# openfc.net
KiCad netlist of a schematic drawn in EAGLE
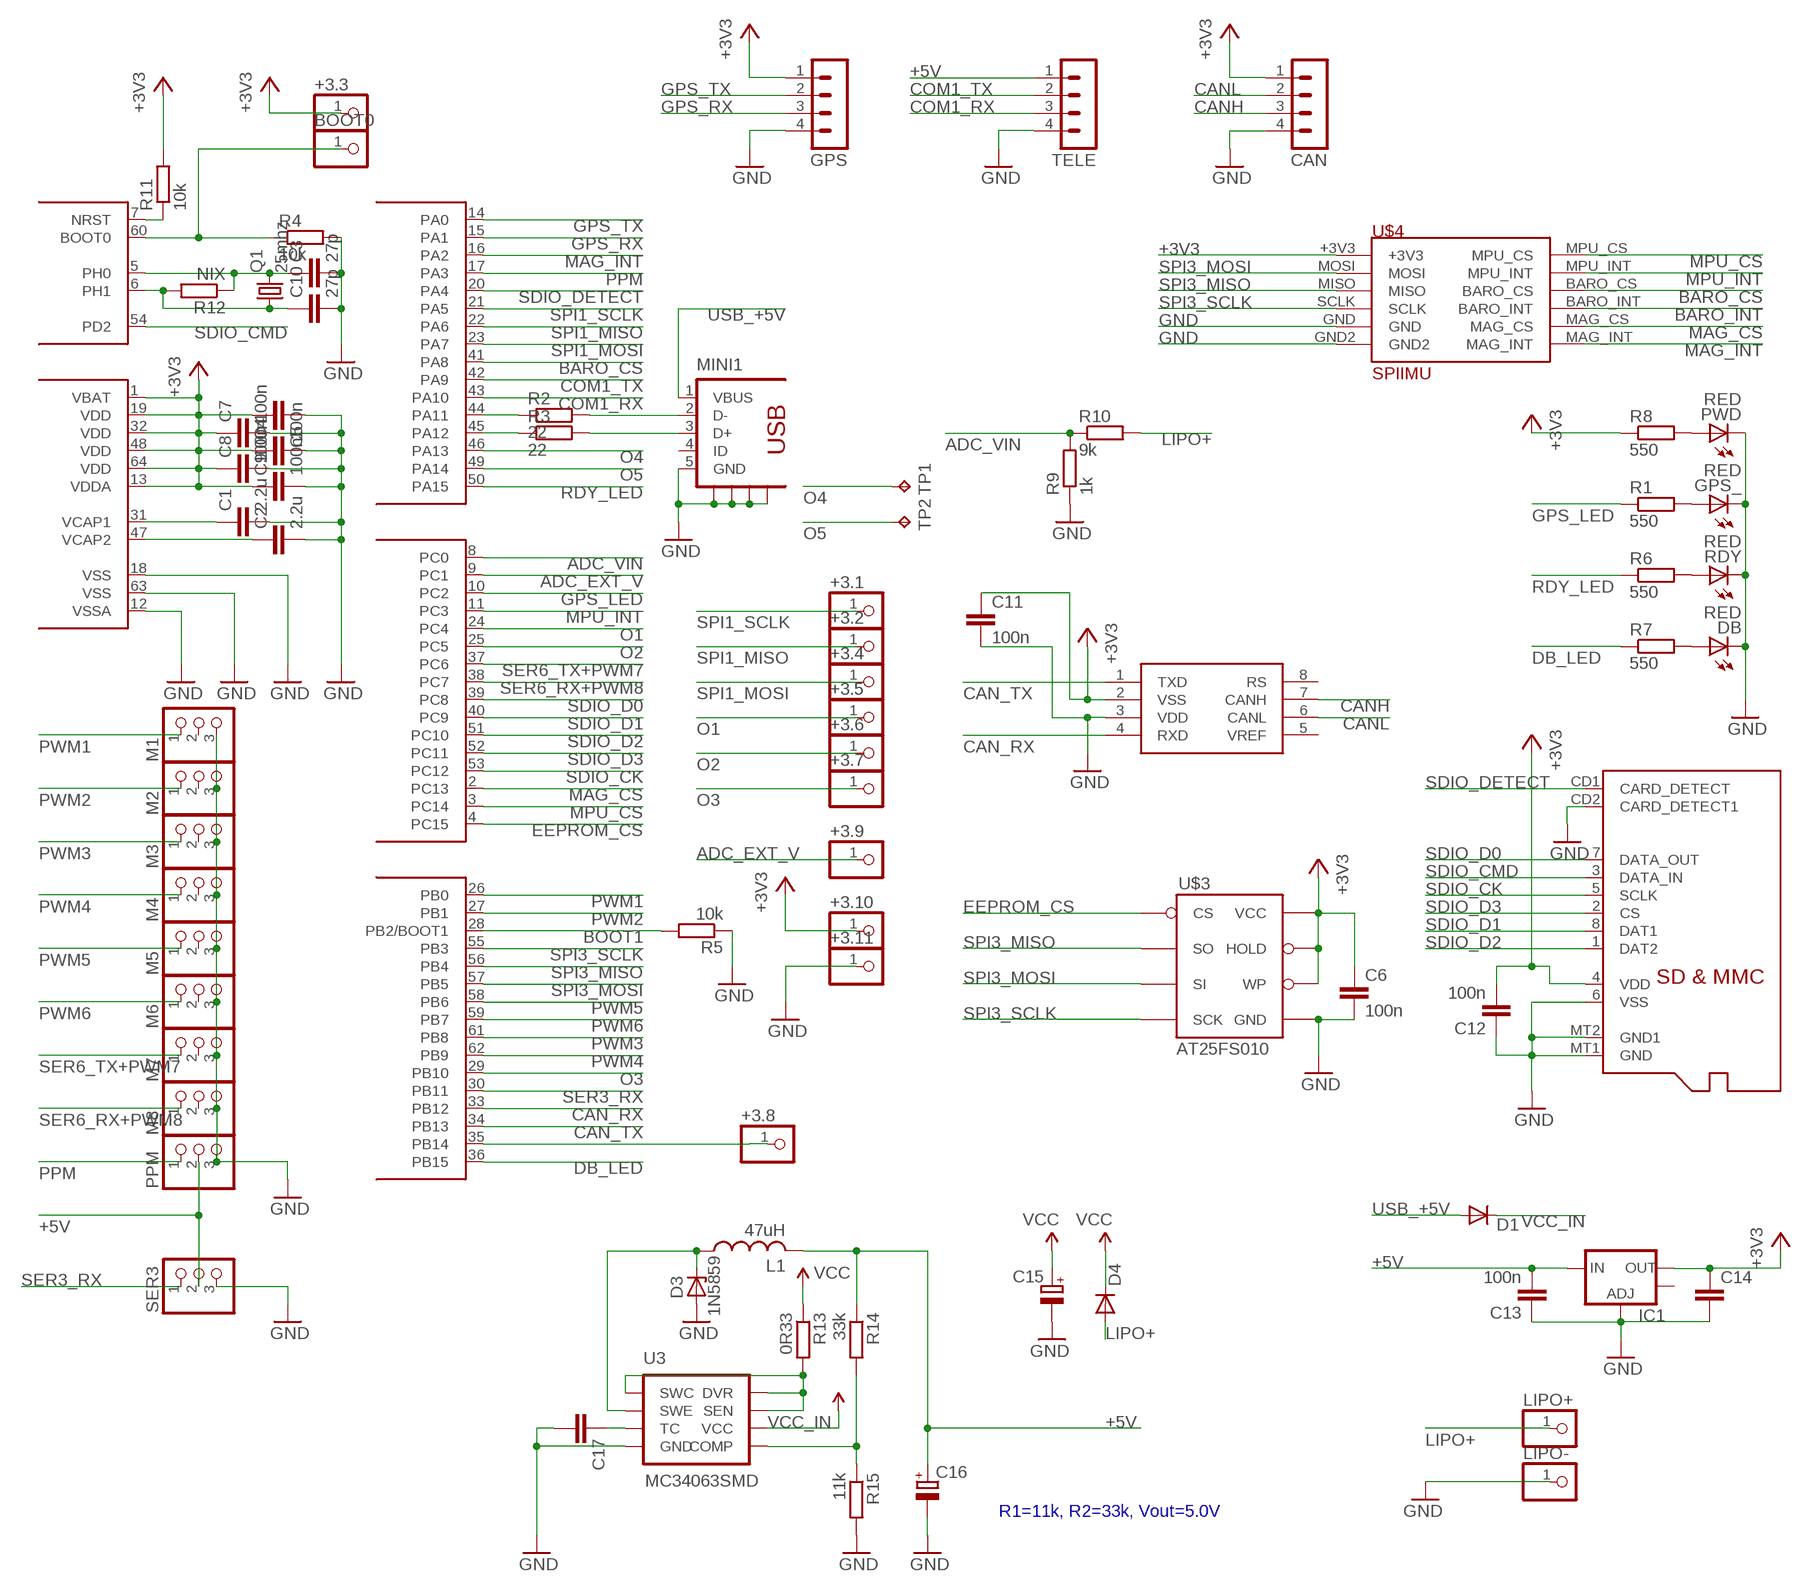
[diagram p0: schematic, sheet 1]

(export (version "E")
  (design (tool "Eeschema 10.0.6"))
  (components
    (comp (ref "+3.1")
      (value "PINHD-1X1")
      (footprint "eagle-import:1X01")
      (libsource (lib "eagle-import") (part "PINHD-1X1"))
    )
    (comp (ref "+3.2")
      (value "PINHD-1X1")
      (footprint "eagle-import:1X01")
      (libsource (lib "eagle-import") (part "PINHD-1X1"))
    )
    (comp (ref "+3.3")
      (value "PINHD-1X1")
      (footprint "eagle-import:1X01")
      (libsource (lib "eagle-import") (part "PINHD-1X1"))
    )
    (comp (ref "+3.4")
      (value "PINHD-1X1")
      (footprint "eagle-import:1X01")
      (libsource (lib "eagle-import") (part "PINHD-1X1"))
    )
    (comp (ref "+3.5")
      (value "PINHD-1X1")
      (footprint "eagle-import:1X01")
      (libsource (lib "eagle-import") (part "PINHD-1X1"))
    )
    (comp (ref "+3.6")
      (value "PINHD-1X1")
      (footprint "eagle-import:1X01")
      (libsource (lib "eagle-import") (part "PINHD-1X1"))
    )
    (comp (ref "+3.7")
      (value "PINHD-1X1")
      (footprint "eagle-import:1X01")
      (libsource (lib "eagle-import") (part "PINHD-1X1"))
    )
    (comp (ref "+3.8")
      (value "PINHD-1X1")
      (footprint "eagle-import:1X01")
      (libsource (lib "eagle-import") (part "PINHD-1X1"))
    )
    (comp (ref "+3.9")
      (value "PINHD-1X1")
      (footprint "eagle-import:1X01")
      (libsource (lib "eagle-import") (part "PINHD-1X1"))
    )
    (comp (ref "+3.10")
      (value "PINHD-1X1")
      (footprint "eagle-import:1X01")
      (libsource (lib "eagle-import") (part "PINHD-1X1"))
    )
    (comp (ref "+3.11")
      (value "PINHD-1X1")
      (footprint "eagle-import:1X01")
      (libsource (lib "eagle-import") (part "PINHD-1X1"))
    )
    (comp (ref "BOOT0")
      (value "PINHD-1X1")
      (footprint "eagle-import:1X01")
      (libsource (lib "eagle-import") (part "PINHD-1X1"))
    )
    (comp (ref "C1")
      (value "2.2u")
      (footprint "eagle-import:C0603")
      (libsource (lib "eagle-import") (part "C-EUC0603"))
    )
    (comp (ref "C2")
      (value "2.2u")
      (footprint "eagle-import:C0603")
      (libsource (lib "eagle-import") (part "C-EUC0603"))
    )
    (comp (ref "C3")
      (value "27p")
      (footprint "eagle-import:C0603")
      (libsource (lib "eagle-import") (part "C-EUC0603"))
    )
    (comp (ref "C4")
      (value "100n")
      (footprint "eagle-import:C0603")
      (libsource (lib "eagle-import") (part "C-EUC0603"))
    )
    (comp (ref "C5")
      (value "100n")
      (footprint "eagle-import:C0603")
      (libsource (lib "eagle-import") (part "C-EUC0603"))
    )
    (comp (ref "C6")
      (value "100n")
      (footprint "eagle-import:C0603")
      (libsource (lib "eagle-import") (part "C-EUC0603"))
    )
    (comp (ref "C7")
      (value "100n")
      (footprint "eagle-import:C0603")
      (libsource (lib "eagle-import") (part "C-EUC0603"))
    )
    (comp (ref "C8")
      (value "100n")
      (footprint "eagle-import:C0603")
      (libsource (lib "eagle-import") (part "C-EUC0603"))
    )
    (comp (ref "C9")
      (value "100n")
      (footprint "eagle-import:C0603")
      (libsource (lib "eagle-import") (part "C-EUC0603"))
    )
    (comp (ref "C10")
      (value "27p")
      (footprint "eagle-import:C0603")
      (libsource (lib "eagle-import") (part "C-EUC0603"))
    )
    (comp (ref "C11")
      (value "100n")
      (footprint "eagle-import:C0603")
      (libsource (lib "eagle-import") (part "C-EUC0603"))
    )
    (comp (ref "C12")
      (value "100n")
      (footprint "eagle-import:C0603")
      (libsource (lib "eagle-import") (part "C-EUC0603"))
    )
    (comp (ref "C13")
      (value "100n")
      (footprint "eagle-import:C0603")
      (libsource (lib "eagle-import") (part "C-EUC0603"))
    )
    (comp (ref "C14")
      (value "C-EUC1206")
      (footprint "eagle-import:C1206")
      (libsource (lib "eagle-import") (part "C-EUC1206"))
    )
    (comp (ref "C15")
      (value "CPOL-EUB/3528-21R")
      (footprint "eagle-import:B_3528-21R")
      (libsource (lib "eagle-import") (part "CPOL-EUB/3528-21R"))
    )
    (comp (ref "C16")
      (value "CPOL-EUB/3528-21R")
      (footprint "eagle-import:B_3528-21R")
      (libsource (lib "eagle-import") (part "CPOL-EUB/3528-21R"))
    )
    (comp (ref "C17")
      (value "C-EUC0603")
      (footprint "eagle-import:C0603")
      (libsource (lib "eagle-import") (part "C-EUC0603"))
    )
    (comp (ref "CAN")
      (value "MA04-1")
      (footprint "eagle-import:MA04-1")
      (fields (field (name "OC_FARNELL") "unknown") (field (name "OC_NEWARK") "unknown"))
      (libsource (lib "eagle-import") (part "MA04-1"))
    )
    (comp (ref "D1")
      (value "DIODE-SMB")
      (footprint "eagle-import:SMB")
      (libsource (lib "eagle-import") (part "DIODE-SMB"))
    )
    (comp (ref "D3")
      (value "1N5859")
      (footprint "eagle-import:SMB")
      (libsource (lib "eagle-import") (part "ZENER-DIODESMB"))
    )
    (comp (ref "D4")
      (value "DIODE-SMB")
      (footprint "eagle-import:SMB")
      (libsource (lib "eagle-import") (part "DIODE-SMB"))
    )
    (comp (ref "DB")
      (value "RED")
      (footprint "eagle-import:LED-0603")
      (fields (field (name "PROD_ID") "DIO-00819"))
      (libsource (lib "eagle-import") (part "LED-RED0603"))
    )
    (comp (ref "GPS")
      (value "MA04-1")
      (footprint "eagle-import:MA04-1")
      (libsource (lib "eagle-import") (part "MA04-1"))
    )
    (comp (ref "GPS_")
      (value "RED")
      (footprint "eagle-import:LED-0603")
      (fields (field (name "PROD_ID") "DIO-00819"))
      (libsource (lib "eagle-import") (part "LED-RED0603"))
    )
    (comp (ref "IC1")
      (value "V_REG_LM1117SOT223")
      (footprint "eagle-import:SOT223")
      (libsource (lib "eagle-import") (part "V_REG_LM1117SOT223"))
    )
    (comp (ref "L1")
      (value "47uH")
      (footprint "eagle-import:L1812")
      (libsource (lib "eagle-import") (part "L-USL1812"))
    )
    (comp (ref "LIPO+")
      (value "PINHD-1X1")
      (footprint "eagle-import:1X01")
      (libsource (lib "eagle-import") (part "PINHD-1X1"))
    )
    (comp (ref "LIPO-")
      (value "PINHD-1X1")
      (footprint "eagle-import:1X01")
      (libsource (lib "eagle-import") (part "PINHD-1X1"))
    )
    (comp (ref "M1")
      (value "PINHD-1X3")
      (footprint "eagle-import:1X03")
      (libsource (lib "eagle-import") (part "PINHD-1X3"))
    )
    (comp (ref "M2")
      (value "PINHD-1X3")
      (footprint "eagle-import:1X03")
      (libsource (lib "eagle-import") (part "PINHD-1X3"))
    )
    (comp (ref "M3")
      (value "PINHD-1X3")
      (footprint "eagle-import:1X03")
      (libsource (lib "eagle-import") (part "PINHD-1X3"))
    )
    (comp (ref "M4")
      (value "PINHD-1X3")
      (footprint "eagle-import:1X03")
      (libsource (lib "eagle-import") (part "PINHD-1X3"))
    )
    (comp (ref "M5")
      (value "PINHD-1X3")
      (footprint "eagle-import:1X03")
      (libsource (lib "eagle-import") (part "PINHD-1X3"))
    )
    (comp (ref "M6")
      (value "PINHD-1X3")
      (footprint "eagle-import:1X03")
      (libsource (lib "eagle-import") (part "PINHD-1X3"))
    )
    (comp (ref "M7")
      (value "PINHD-1X3")
      (footprint "eagle-import:1X03")
      (libsource (lib "eagle-import") (part "PINHD-1X3"))
    )
    (comp (ref "M8")
      (value "PINHD-1X3")
      (footprint "eagle-import:1X03")
      (libsource (lib "eagle-import") (part "PINHD-1X3"))
    )
    (comp (ref "MINI1")
      (value "USB-5P")
      (footprint "eagle-import:USB-MINI-B")
      (libsource (lib "eagle-import") (part "USB-5P"))
    )
    (comp (ref "PPM")
      (value "PINHD-1X3")
      (footprint "eagle-import:1X03")
      (libsource (lib "eagle-import") (part "PINHD-1X3"))
    )
    (comp (ref "PWD")
      (value "RED")
      (footprint "eagle-import:LED-0603")
      (fields (field (name "PROD_ID") "DIO-00819"))
      (libsource (lib "eagle-import") (part "LED-RED0603"))
    )
    (comp (ref "Q1")
      (value "25mhz")
      (footprint "eagle-import:CTS406")
      (fields (field (name "OC_FARNELL") "unknown"))
      (libsource (lib "eagle-import") (part "CRYSTALCTS406"))
    )
    (comp (ref "R1")
      (value "550")
      (footprint "eagle-import:R0603")
      (libsource (lib "eagle-import") (part "R-EU_R0603"))
    )
    (comp (ref "R2")
      (value "22")
      (footprint "eagle-import:R0603")
      (libsource (lib "eagle-import") (part "R-EU_R0603"))
    )
    (comp (ref "R3")
      (value "22")
      (footprint "eagle-import:R0603")
      (libsource (lib "eagle-import") (part "R-EU_R0603"))
    )
    (comp (ref "R4")
      (value "10k")
      (footprint "eagle-import:R0603")
      (libsource (lib "eagle-import") (part "R-EU_R0603"))
    )
    (comp (ref "R5")
      (value "10k")
      (footprint "eagle-import:R0603")
      (libsource (lib "eagle-import") (part "R-EU_R0603"))
    )
    (comp (ref "R6")
      (value "550")
      (footprint "eagle-import:R0603")
      (libsource (lib "eagle-import") (part "R-EU_R0603"))
    )
    (comp (ref "R7")
      (value "550")
      (footprint "eagle-import:R0603")
      (libsource (lib "eagle-import") (part "R-EU_R0603"))
    )
    (comp (ref "R8")
      (value "550")
      (footprint "eagle-import:R0603")
      (libsource (lib "eagle-import") (part "R-EU_R0603"))
    )
    (comp (ref "R9")
      (value "1k")
      (footprint "eagle-import:R0603")
      (libsource (lib "eagle-import") (part "R-EU_R0603"))
    )
    (comp (ref "R10")
      (value "9k")
      (footprint "eagle-import:R0603")
      (libsource (lib "eagle-import") (part "R-EU_R0603"))
    )
    (comp (ref "R11")
      (value "10k")
      (footprint "eagle-import:R0603")
      (libsource (lib "eagle-import") (part "R-EU_R0603"))
    )
    (comp (ref "R12")
      (value "NIX")
      (footprint "eagle-import:R0603")
      (libsource (lib "eagle-import") (part "R-EU_R0603"))
    )
    (comp (ref "R13")
      (value "0R33")
      (footprint "eagle-import:R0603")
      (libsource (lib "eagle-import") (part "R-EU_R0603"))
    )
    (comp (ref "R14")
      (value "33k")
      (footprint "eagle-import:R0603")
      (libsource (lib "eagle-import") (part "R-EU_R0603"))
    )
    (comp (ref "R15")
      (value "11k")
      (footprint "eagle-import:R0603")
      (libsource (lib "eagle-import") (part "R-EU_R0603"))
    )
    (comp (ref "RDY")
      (value "RED")
      (footprint "eagle-import:LED-0603")
      (fields (field (name "PROD_ID") "DIO-00819"))
      (libsource (lib "eagle-import") (part "LED-RED0603"))
    )
    (comp (ref "SER3")
      (value "PINHD-1X3")
      (footprint "eagle-import:1X03")
      (libsource (lib "eagle-import") (part "PINHD-1X3"))
    )
    (comp (ref "TELE")
      (value "MA04-1")
      (footprint "eagle-import:MA04-1")
      (libsource (lib "eagle-import") (part "MA04-1"))
    )
    (comp (ref "TP1")
      (value "TPTP14SQ")
      (footprint "eagle-import:TP14SQ")
      (libsource (lib "eagle-import") (part "TPTP14SQ"))
    )
    (comp (ref "TP2")
      (value "TPTP14SQ")
      (footprint "eagle-import:TP14SQ")
      (libsource (lib "eagle-import") (part "TPTP14SQ"))
    )
    (comp (ref "U$2")
      (value "MICROSD")
      (footprint "eagle-import:MICROSD")
      (libsource (lib "eagle-import") (part "MICROSD"))
    )
    (comp (ref "U$3")
      (value "AT25FS010")
      (footprint "eagle-import:SO08WIDE")
      (libsource (lib "eagle-import") (part "AT25FS010"))
    )
    (comp (ref "U$4")
      (value "SPIIMU")
      (footprint "eagle-import:SPIIMU")
      (libsource (lib "eagle-import") (part "SPIIMU"))
    )
    (comp (ref "U1")
      (value "STM32F4-64")
      (footprint "eagle-import:SQFP-S-10X10-64")
      (libsource (lib "eagle-import") (part "STM32F4-64"))
    )
    (comp (ref "U3")
      (value "MC34063SMD")
      (footprint "eagle-import:SO08")
      (libsource (lib "eagle-import") (part "MC34063SMD"))
    )
    (comp (ref "U4")
      (value "MCP2551")
      (footprint "eagle-import:SO08")
      (libsource (lib "eagle-import") (part "MCP2551"))
    )
  )
  (nets
    (net (code "1") (name "+3V3") (class "Default")
      (node (ref "+3.10") (pin "1") (pinfunction "1_1") (pintype "passive"))
      (node (ref "+3.3") (pin "1") (pinfunction "1_1") (pintype "passive"))
      (node (ref "C11") (pin "1") (pinfunction "1_1") (pintype "passive"))
      (node (ref "C12") (pin "2") (pinfunction "2_2") (pintype "passive"))
      (node (ref "C14") (pin "1") (pinfunction "1_1") (pintype "passive"))
      (node (ref "C4") (pin "1") (pinfunction "1_1") (pintype "passive"))
      (node (ref "C5") (pin "2") (pinfunction "2_2") (pintype "passive"))
      (node (ref "C6") (pin "1") (pinfunction "1_1") (pintype "passive"))
      (node (ref "C7") (pin "1") (pinfunction "1_1") (pintype "passive"))
      (node (ref "C8") (pin "1") (pinfunction "1_1") (pintype "passive"))
      (node (ref "C9") (pin "1") (pinfunction "1_1") (pintype "passive"))
      (node (ref "CAN") (pin "1") (pinfunction "1_1") (pintype "passive"))
      (node (ref "GPS") (pin "1") (pinfunction "1_1") (pintype "passive"))
      (node (ref "IC1") (pin "2") (pinfunction "OUT_2") (pintype "output"))
      (node (ref "R11") (pin "2") (pinfunction "2_2") (pintype "passive"))
      (node (ref "R8") (pin "1") (pinfunction "1_1") (pintype "passive"))
      (node (ref "U$2") (pin "4") (pinfunction "VDD_4") (pintype "power_in"))
      (node (ref "U$3") (pin "3") (pinfunction "WP_3") (pintype "bidirectional"))
      (node (ref "U$3") (pin "7") (pinfunction "HOLD_7") (pintype "bidirectional"))
      (node (ref "U$3") (pin "8") (pinfunction "VCC_8") (pintype "bidirectional"))
      (node (ref "U$4") (pin "+3V3") (pinfunction "+3V3_+3V3") (pintype "power_in"))
      (node (ref "U1") (pin "1") (pinfunction "VBAT_1") (pintype "power_in"))
      (node (ref "U1") (pin "13") (pinfunction "VDDA_13") (pintype "power_in"))
      (node (ref "U1") (pin "19") (pinfunction "VDD_19") (pintype "power_in"))
      (node (ref "U1") (pin "32") (pinfunction "VDD_32") (pintype "power_in"))
      (node (ref "U1") (pin "48") (pinfunction "VDD_48") (pintype "power_in"))
      (node (ref "U1") (pin "64") (pinfunction "VDD_64") (pintype "power_in"))
      (node (ref "U4") (pin "2") (pinfunction "VSS_2") (pintype "bidirectional"))
    )
    (net (code "2") (name "/+5V") (class "Default")
      (node (ref "C13") (pin "2") (pinfunction "2_2") (pintype "passive"))
      (node (ref "C16") (pin "+") (pinfunction "+_+") (pintype "passive"))
      (node (ref "IC1") (pin "3") (pinfunction "IN_3") (pintype "input"))
      (node (ref "L1") (pin "2") (pinfunction "2_2") (pintype "passive"))
      (node (ref "PPM") (pin "2") (pinfunction "2_2") (pintype "passive"))
      (node (ref "R14") (pin "1") (pinfunction "1_1") (pintype "passive"))
      (node (ref "SER3") (pin "2") (pinfunction "2_2") (pintype "passive"))
      (node (ref "TELE") (pin "1") (pinfunction "1_1") (pintype "passive"))
    )
    (net (code "3") (name "/ADC_EXT_V") (class "Default")
      (node (ref "+3.9") (pin "1") (pinfunction "1_1") (pintype "passive"))
      (node (ref "U1") (pin "9") (pinfunction "PC1_9") (pintype "bidirectional"))
    )
    (net (code "4") (name "/ADC_VIN") (class "Default")
      (node (ref "R10") (pin "1") (pinfunction "1_1") (pintype "passive"))
      (node (ref "R9") (pin "2") (pinfunction "2_2") (pintype "passive"))
      (node (ref "U1") (pin "8") (pinfunction "PC0_8") (pintype "bidirectional"))
    )
    (net (code "5") (name "/BARO_CS") (class "Default")
      (node (ref "U$4") (pin "BARO_CS") (pinfunction "BARO_CS_BARO_CS") (pintype "bidirectional"))
      (node (ref "U1") (pin "41") (pinfunction "PA8_41") (pintype "bidirectional"))
    )
    (net (code "6") (name "/BARO_INT") (class "Default")
      (node (ref "U$4") (pin "BARO_INT") (pinfunction "BARO_INT_BARO_INT") (pintype "bidirectional"))
    )
    (net (code "7") (name "/BOOT1") (class "Default")
      (node (ref "R5") (pin "2") (pinfunction "2_2") (pintype "passive"))
      (node (ref "U1") (pin "28") (pinfunction "PB2/BOOT1_28") (pintype "bidirectional"))
    )
    (net (code "8") (name "/CANH") (class "Default")
      (node (ref "CAN") (pin "3") (pinfunction "3_3") (pintype "passive"))
      (node (ref "U4") (pin "7") (pinfunction "CANH_7") (pintype "bidirectional"))
    )
    (net (code "9") (name "/CANL") (class "Default")
      (node (ref "CAN") (pin "2") (pinfunction "2_2") (pintype "passive"))
      (node (ref "U4") (pin "6") (pinfunction "CANL_6") (pintype "bidirectional"))
    )
    (net (code "10") (name "/CAN_RX") (class "Default")
      (node (ref "U1") (pin "33") (pinfunction "PB12_33") (pintype "bidirectional"))
      (node (ref "U4") (pin "4") (pinfunction "RXD_4") (pintype "bidirectional"))
    )
    (net (code "11") (name "/CAN_TX") (class "Default")
      (node (ref "U1") (pin "34") (pinfunction "PB13_34") (pintype "bidirectional"))
      (node (ref "U4") (pin "1") (pinfunction "TXD_1") (pintype "bidirectional"))
    )
    (net (code "12") (name "/COM1_RX") (class "Default")
      (node (ref "TELE") (pin "3") (pinfunction "3_3") (pintype "passive"))
      (node (ref "U1") (pin "43") (pinfunction "PA10_43") (pintype "bidirectional"))
    )
    (net (code "13") (name "/COM1_TX") (class "Default")
      (node (ref "TELE") (pin "2") (pinfunction "2_2") (pintype "passive"))
      (node (ref "U1") (pin "42") (pinfunction "PA9_42") (pintype "bidirectional"))
    )
    (net (code "14") (name "/DB_LED") (class "Default")
      (node (ref "R7") (pin "1") (pinfunction "1_1") (pintype "passive"))
      (node (ref "U1") (pin "36") (pinfunction "PB15_36") (pintype "bidirectional"))
    )
    (net (code "15") (name "/EEPROM_CS") (class "Default")
      (node (ref "U$3") (pin "1") (pinfunction "CS_1") (pintype "bidirectional"))
      (node (ref "U1") (pin "4") (pinfunction "PC15_4") (pintype "bidirectional"))
    )
    (net (code "16") (name "/GPS_LED") (class "Default")
      (node (ref "R1") (pin "1") (pinfunction "1_1") (pintype "passive"))
      (node (ref "U1") (pin "10") (pinfunction "PC2_10") (pintype "bidirectional"))
    )
    (net (code "17") (name "/GPS_RX") (class "Default")
      (node (ref "GPS") (pin "3") (pinfunction "3_3") (pintype "passive"))
      (node (ref "U1") (pin "15") (pinfunction "PA1_15") (pintype "bidirectional"))
    )
    (net (code "18") (name "/GPS_TX") (class "Default")
      (node (ref "GPS") (pin "2") (pinfunction "2_2") (pintype "passive"))
      (node (ref "U1") (pin "14") (pinfunction "PA0_14") (pintype "bidirectional"))
    )
    (net (code "19") (name "/LIPO+") (class "Default")
      (node (ref "D4") (pin "A") (pinfunction "A_A") (pintype "passive"))
      (node (ref "LIPO+") (pin "1") (pinfunction "1_1") (pintype "passive"))
      (node (ref "R10") (pin "2") (pinfunction "2_2") (pintype "passive"))
    )
    (net (code "20") (name "/MAG_CS") (class "Default")
      (node (ref "U$4") (pin "MAG_CS") (pinfunction "MAG_CS_MAG_CS") (pintype "bidirectional"))
      (node (ref "U1") (pin "2") (pinfunction "PC13_2") (pintype "bidirectional"))
    )
    (net (code "21") (name "/MAG_INT") (class "Default")
      (node (ref "U$4") (pin "MAG_INT") (pinfunction "MAG_INT_MAG_INT") (pintype "bidirectional"))
      (node (ref "U1") (pin "16") (pinfunction "PA2_16") (pintype "bidirectional"))
    )
    (net (code "22") (name "/MPU_CS") (class "Default")
      (node (ref "U$4") (pin "MPU_CS") (pinfunction "MPU_CS_MPU_CS") (pintype "bidirectional"))
      (node (ref "U1") (pin "3") (pinfunction "PC14_3") (pintype "bidirectional"))
    )
    (net (code "23") (name "/MPU_INT") (class "Default")
      (node (ref "U$4") (pin "MPU_INT") (pinfunction "MPU_INT_MPU_INT") (pintype "bidirectional"))
      (node (ref "U1") (pin "11") (pinfunction "PC3_11") (pintype "bidirectional"))
    )
    (net (code "24") (name "/O1") (class "Default")
      (node (ref "+3.5") (pin "1") (pinfunction "1_1") (pintype "passive"))
      (node (ref "U1") (pin "24") (pinfunction "PC4_24") (pintype "bidirectional"))
    )
    (net (code "25") (name "/O2") (class "Default")
      (node (ref "+3.6") (pin "1") (pinfunction "1_1") (pintype "passive"))
      (node (ref "U1") (pin "25") (pinfunction "PC5_25") (pintype "bidirectional"))
    )
    (net (code "26") (name "/O3") (class "Default")
      (node (ref "+3.7") (pin "1") (pinfunction "1_1") (pintype "passive"))
      (node (ref "U1") (pin "29") (pinfunction "PB10_29") (pintype "bidirectional"))
    )
    (net (code "27") (name "/O4") (class "Default")
      (node (ref "TP1") (pin "TP") (pinfunction "TP_TP") (pintype "input"))
      (node (ref "U1") (pin "46") (pinfunction "PA13_46") (pintype "bidirectional"))
    )
    (net (code "28") (name "/O5") (class "Default")
      (node (ref "TP2") (pin "TP") (pinfunction "TP_TP") (pintype "input"))
      (node (ref "U1") (pin "49") (pinfunction "PA14_49") (pintype "bidirectional"))
    )
    (net (code "29") (name "/PPM") (class "Default")
      (node (ref "PPM") (pin "1") (pinfunction "1_1") (pintype "passive"))
      (node (ref "U1") (pin "17") (pinfunction "PA3_17") (pintype "bidirectional"))
    )
    (net (code "30") (name "/PWM1") (class "Default")
      (node (ref "M1") (pin "1") (pinfunction "1_1") (pintype "passive"))
      (node (ref "U1") (pin "26") (pinfunction "PB0_26") (pintype "bidirectional"))
    )
    (net (code "31") (name "/PWM2") (class "Default")
      (node (ref "M2") (pin "1") (pinfunction "1_1") (pintype "passive"))
      (node (ref "U1") (pin "27") (pinfunction "PB1_27") (pintype "bidirectional"))
    )
    (net (code "32") (name "/PWM3") (class "Default")
      (node (ref "M3") (pin "1") (pinfunction "1_1") (pintype "passive"))
      (node (ref "U1") (pin "61") (pinfunction "PB8_61") (pintype "bidirectional"))
    )
    (net (code "33") (name "/PWM4") (class "Default")
      (node (ref "M4") (pin "1") (pinfunction "1_1") (pintype "passive"))
      (node (ref "U1") (pin "62") (pinfunction "PB9_62") (pintype "bidirectional"))
    )
    (net (code "34") (name "/PWM5") (class "Default")
      (node (ref "M5") (pin "1") (pinfunction "1_1") (pintype "passive"))
      (node (ref "U1") (pin "58") (pinfunction "PB6_58") (pintype "bidirectional"))
    )
    (net (code "35") (name "/PWM6") (class "Default")
      (node (ref "M6") (pin "1") (pinfunction "1_1") (pintype "passive"))
      (node (ref "U1") (pin "59") (pinfunction "PB7_59") (pintype "bidirectional"))
    )
    (net (code "36") (name "/RDY_LED") (class "Default")
      (node (ref "R6") (pin "1") (pinfunction "1_1") (pintype "passive"))
      (node (ref "U1") (pin "50") (pinfunction "PA15_50") (pintype "bidirectional"))
    )
    (net (code "37") (name "/SDIO_CK") (class "Default")
      (node (ref "U$2") (pin "5") (pinfunction "SCLK_5") (pintype "input"))
      (node (ref "U1") (pin "53") (pinfunction "PC12_53") (pintype "bidirectional"))
    )
    (net (code "38") (name "/SDIO_CMD") (class "Default")
      (node (ref "U$2") (pin "3") (pinfunction "DATA_IN_3") (pintype "input"))
      (node (ref "U1") (pin "54") (pinfunction "PD2_54") (pintype "bidirectional"))
    )
    (net (code "39") (name "/SDIO_D0") (class "Default")
      (node (ref "U$2") (pin "7") (pinfunction "DATA_OUT_7") (pintype "output"))
      (node (ref "U1") (pin "39") (pinfunction "PC8_39") (pintype "bidirectional"))
    )
    (net (code "40") (name "/SDIO_D1") (class "Default")
      (node (ref "U$2") (pin "8") (pinfunction "DAT1_8") (pintype "bidirectional"))
      (node (ref "U1") (pin "40") (pinfunction "PC9_40") (pintype "bidirectional"))
    )
    (net (code "41") (name "/SDIO_D2") (class "Default")
      (node (ref "U$2") (pin "1") (pinfunction "DAT2_1") (pintype "bidirectional"))
      (node (ref "U1") (pin "51") (pinfunction "PC10_51") (pintype "bidirectional"))
    )
    (net (code "42") (name "/SDIO_D3") (class "Default")
      (node (ref "U$2") (pin "2") (pinfunction "CS_2") (pintype "input"))
      (node (ref "U1") (pin "52") (pinfunction "PC11_52") (pintype "bidirectional"))
    )
    (net (code "43") (name "/SDIO_DETECT") (class "Default")
      (node (ref "U$2") (pin "CD1") (pinfunction "CARD_DETECT_CD1") (pintype "passive"))
      (node (ref "U1") (pin "20") (pinfunction "PA4_20") (pintype "bidirectional"))
    )
    (net (code "44") (name "/SER3_RX") (class "Default")
      (node (ref "SER3") (pin "1") (pinfunction "1_1") (pintype "passive"))
      (node (ref "U1") (pin "30") (pinfunction "PB11_30") (pintype "bidirectional"))
    )
    (net (code "45") (name "/SER6_RX+PWM8") (class "Default")
      (node (ref "M8") (pin "1") (pinfunction "1_1") (pintype "passive"))
      (node (ref "U1") (pin "38") (pinfunction "PC7_38") (pintype "bidirectional"))
    )
    (net (code "46") (name "/SER6_TX+PWM7") (class "Default")
      (node (ref "M7") (pin "1") (pinfunction "1_1") (pintype "passive"))
      (node (ref "U1") (pin "37") (pinfunction "PC6_37") (pintype "bidirectional"))
    )
    (net (code "47") (name "/SPI1_MISO") (class "Default")
      (node (ref "+3.2") (pin "1") (pinfunction "1_1") (pintype "passive"))
      (node (ref "U1") (pin "22") (pinfunction "PA6_22") (pintype "bidirectional"))
    )
    (net (code "48") (name "/SPI1_MOSI") (class "Default")
      (node (ref "+3.4") (pin "1") (pinfunction "1_1") (pintype "passive"))
      (node (ref "U1") (pin "23") (pinfunction "PA7_23") (pintype "bidirectional"))
    )
    (net (code "49") (name "/SPI1_SCLK") (class "Default")
      (node (ref "+3.1") (pin "1") (pinfunction "1_1") (pintype "passive"))
      (node (ref "U1") (pin "21") (pinfunction "PA5_21") (pintype "bidirectional"))
    )
    (net (code "50") (name "/SPI3_MISO") (class "Default")
      (node (ref "U$3") (pin "2") (pinfunction "SO_2") (pintype "bidirectional"))
      (node (ref "U$4") (pin "MISO") (pinfunction "MISO_MISO") (pintype "bidirectional"))
      (node (ref "U1") (pin "56") (pinfunction "PB4_56") (pintype "bidirectional"))
    )
    (net (code "51") (name "/SPI3_MOSI") (class "Default")
      (node (ref "U$3") (pin "5") (pinfunction "SI_5") (pintype "bidirectional"))
      (node (ref "U$4") (pin "MOSI") (pinfunction "MOSI_MOSI") (pintype "bidirectional"))
      (node (ref "U1") (pin "57") (pinfunction "PB5_57") (pintype "bidirectional"))
    )
    (net (code "52") (name "/SPI3_SCLK") (class "Default")
      (node (ref "U$3") (pin "6") (pinfunction "SCK_6") (pintype "bidirectional"))
      (node (ref "U$4") (pin "SCLK") (pinfunction "SCLK_SCLK") (pintype "bidirectional"))
      (node (ref "U1") (pin "55") (pinfunction "PB3_55") (pintype "bidirectional"))
    )
    (net (code "53") (name "/USB_+5V") (class "Default")
      (node (ref "D1") (pin "A") (pinfunction "A_A") (pintype "passive"))
      (node (ref "MINI1") (pin "1") (pinfunction "VBUS_1") (pintype "passive"))
    )
    (net (code "54") (name "GND") (class "Default")
      (node (ref "+3.11") (pin "1") (pinfunction "1_1") (pintype "passive"))
      (node (ref "C1") (pin "2") (pinfunction "2_2") (pintype "passive"))
      (node (ref "C10") (pin "2") (pinfunction "2_2") (pintype "passive"))
      (node (ref "C11") (pin "2") (pinfunction "2_2") (pintype "passive"))
      (node (ref "C12") (pin "1") (pinfunction "1_1") (pintype "passive"))
      (node (ref "C13") (pin "1") (pinfunction "1_1") (pintype "passive"))
      (node (ref "C14") (pin "2") (pinfunction "2_2") (pintype "passive"))
      (node (ref "C15") (pin "-") (pinfunction "-_-") (pintype "passive"))
      (node (ref "C16") (pin "-") (pinfunction "-_-") (pintype "passive"))
      (node (ref "C17") (pin "2") (pinfunction "2_2") (pintype "passive"))
      (node (ref "C2") (pin "2") (pinfunction "2_2") (pintype "passive"))
      (node (ref "C3") (pin "2") (pinfunction "2_2") (pintype "passive"))
      (node (ref "C4") (pin "2") (pinfunction "2_2") (pintype "passive"))
      (node (ref "C5") (pin "1") (pinfunction "1_1") (pintype "passive"))
      (node (ref "C6") (pin "2") (pinfunction "2_2") (pintype "passive"))
      (node (ref "C7") (pin "2") (pinfunction "2_2") (pintype "passive"))
      (node (ref "C8") (pin "2") (pinfunction "2_2") (pintype "passive"))
      (node (ref "C9") (pin "2") (pinfunction "2_2") (pintype "passive"))
      (node (ref "CAN") (pin "4") (pinfunction "4_4") (pintype "passive"))
      (node (ref "D3") (pin "A") (pinfunction "A_A") (pintype "passive"))
      (node (ref "DB") (pin "C") (pinfunction "C_C") (pintype "passive"))
      (node (ref "GPS") (pin "4") (pinfunction "4_4") (pintype "passive"))
      (node (ref "GPS_") (pin "C") (pinfunction "C_C") (pintype "passive"))
      (node (ref "IC1") (pin "1") (pinfunction "ADJ_1") (pintype "input"))
      (node (ref "LIPO-") (pin "1") (pinfunction "1_1") (pintype "passive"))
      (node (ref "M1") (pin "3") (pinfunction "3_3") (pintype "passive"))
      (node (ref "M2") (pin "3") (pinfunction "3_3") (pintype "passive"))
      (node (ref "M3") (pin "3") (pinfunction "3_3") (pintype "passive"))
      (node (ref "M4") (pin "3") (pinfunction "3_3") (pintype "passive"))
      (node (ref "M5") (pin "3") (pinfunction "3_3") (pintype "passive"))
      (node (ref "M6") (pin "3") (pinfunction "3_3") (pintype "passive"))
      (node (ref "M7") (pin "3") (pinfunction "3_3") (pintype "passive"))
      (node (ref "M8") (pin "3") (pinfunction "3_3") (pintype "passive"))
      (node (ref "MINI1") (pin "5") (pinfunction "GND_5") (pintype "passive"))
      (node (ref "MINI1") (pin "S1") (pinfunction "S1_S1") (pintype "passive"))
      (node (ref "MINI1") (pin "S2") (pinfunction "S2_S2") (pintype "passive"))
      (node (ref "MINI1") (pin "S3") (pinfunction "S3_S3") (pintype "passive"))
      (node (ref "MINI1") (pin "S4") (pinfunction "S4_S4") (pintype "passive"))
      (node (ref "PPM") (pin "3") (pinfunction "3_3") (pintype "passive"))
      (node (ref "PWD") (pin "C") (pinfunction "C_C") (pintype "passive"))
      (node (ref "R15") (pin "2") (pinfunction "2_2") (pintype "passive"))
      (node (ref "R4") (pin "2") (pinfunction "2_2") (pintype "passive"))
      (node (ref "R5") (pin "1") (pinfunction "1_1") (pintype "passive"))
      (node (ref "R9") (pin "1") (pinfunction "1_1") (pintype "passive"))
      (node (ref "RDY") (pin "C") (pinfunction "C_C") (pintype "passive"))
      (node (ref "SER3") (pin "3") (pinfunction "3_3") (pintype "passive"))
      (node (ref "TELE") (pin "4") (pinfunction "4_4") (pintype "passive"))
      (node (ref "U$2") (pin "6") (pinfunction "VSS_6") (pintype "power_in"))
      (node (ref "U$2") (pin "CD2") (pinfunction "CARD_DETECT1_CD2") (pintype "passive"))
      (node (ref "U$2") (pin "MT1") (pinfunction "GND_MT1") (pintype "power_in"))
      (node (ref "U$2") (pin "MT2") (pinfunction "GND1_MT2") (pintype "power_in"))
      (node (ref "U$3") (pin "4") (pinfunction "GND_4") (pintype "bidirectional"))
      (node (ref "U$4") (pin "GND") (pinfunction "GND_GND") (pintype "power_in"))
      (node (ref "U$4") (pin "GND2") (pinfunction "GND2_GND2") (pintype "power_in"))
      (node (ref "U1") (pin "12") (pinfunction "VSSA_12") (pintype "power_in"))
      (node (ref "U1") (pin "18") (pinfunction "VSS_18") (pintype "power_in"))
      (node (ref "U1") (pin "63") (pinfunction "VSS_63") (pintype "power_in"))
      (node (ref "U3") (pin "4") (pinfunction "GND_4") (pintype "bidirectional"))
      (node (ref "U4") (pin "3") (pinfunction "VDD_3") (pintype "bidirectional"))
    )
    (net (code "55") (name "Net-(DB-PadA)") (class "Default")
      (node (ref "DB") (pin "A") (pinfunction "A_A") (pintype "passive"))
      (node (ref "R7") (pin "2") (pinfunction "2_2") (pintype "passive"))
    )
    (net (code "56") (name "Net-(GPS_-PadA)") (class "Default")
      (node (ref "GPS_") (pin "A") (pinfunction "A_A") (pintype "passive"))
      (node (ref "R1") (pin "2") (pinfunction "2_2") (pintype "passive"))
    )
    (net (code "57") (name "Net-(MINI1-D+)") (class "Default")
      (node (ref "MINI1") (pin "3") (pinfunction "D+_3") (pintype "passive"))
      (node (ref "R3") (pin "2") (pinfunction "2_2") (pintype "passive"))
    )
    (net (code "58") (name "Net-(MINI1-D-)") (class "Default")
      (node (ref "MINI1") (pin "2") (pinfunction "D-_2") (pintype "passive"))
      (node (ref "R2") (pin "2") (pinfunction "2_2") (pintype "passive"))
    )
    (net (code "59") (name "Net-(PWD-PadA)") (class "Default")
      (node (ref "PWD") (pin "A") (pinfunction "A_A") (pintype "passive"))
      (node (ref "R8") (pin "2") (pinfunction "2_2") (pintype "passive"))
    )
    (net (code "60") (name "Net-(Q1-2)") (class "Default")
      (node (ref "C3") (pin "1") (pinfunction "1_1") (pintype "passive"))
      (node (ref "Q1") (pin "3") (pinfunction "2_3") (pintype "passive"))
      (node (ref "R12") (pin "1") (pinfunction "1_1") (pintype "passive"))
      (node (ref "U1") (pin "5") (pinfunction "PH0_5") (pintype "bidirectional"))
    )
    (net (code "61") (name "Net-(R6-Pad2)") (class "Default")
      (node (ref "R6") (pin "2") (pinfunction "2_2") (pintype "passive"))
      (node (ref "RDY") (pin "A") (pinfunction "A_A") (pintype "passive"))
    )
    (net (code "62") (name "Net-(U1A-VCAP1)") (class "Default")
      (node (ref "C1") (pin "1") (pinfunction "1_1") (pintype "passive"))
      (node (ref "U1") (pin "31") (pinfunction "VCAP1_31") (pintype "passive"))
    )
    (net (code "63") (name "Net-(U1A-VCAP2)") (class "Default")
      (node (ref "C2") (pin "1") (pinfunction "1_1") (pintype "passive"))
      (node (ref "U1") (pin "47") (pinfunction "VCAP2_47") (pintype "passive"))
    )
    (net (code "64") (name "Net-(U1B-PA11)") (class "Default")
      (node (ref "R2") (pin "1") (pinfunction "1_1") (pintype "passive"))
      (node (ref "U1") (pin "44") (pinfunction "PA11_44") (pintype "bidirectional"))
    )
    (net (code "65") (name "Net-(U1B-PA12)") (class "Default")
      (node (ref "R3") (pin "1") (pinfunction "1_1") (pintype "passive"))
      (node (ref "U1") (pin "45") (pinfunction "PA12_45") (pintype "bidirectional"))
    )
    (net (code "66") (name "Net-(U1C-PB14)") (class "Default")
      (node (ref "+3.8") (pin "1") (pinfunction "1_1") (pintype "passive"))
      (node (ref "U1") (pin "35") (pinfunction "PB14_35") (pintype "bidirectional"))
    )
    (net (code "67") (name "Net-(U1E-BOOT0)") (class "Default")
      (node (ref "BOOT0") (pin "1") (pinfunction "1_1") (pintype "passive"))
      (node (ref "R4") (pin "1") (pinfunction "1_1") (pintype "passive"))
      (node (ref "U1") (pin "60") (pinfunction "BOOT0_60") (pintype "bidirectional"))
    )
    (net (code "68") (name "Net-(U1E-NRST)") (class "Default")
      (node (ref "R11") (pin "1") (pinfunction "1_1") (pintype "passive"))
      (node (ref "U1") (pin "7") (pinfunction "NRST_7") (pintype "bidirectional"))
    )
    (net (code "69") (name "Net-(U1E-PH1)") (class "Default")
      (node (ref "C10") (pin "1") (pinfunction "1_1") (pintype "passive"))
      (node (ref "Q1") (pin "1") (pinfunction "1_1") (pintype "passive"))
      (node (ref "R12") (pin "2") (pinfunction "2_2") (pintype "passive"))
      (node (ref "U1") (pin "6") (pinfunction "PH1_6") (pintype "bidirectional"))
    )
    (net (code "70") (name "Net-(U3-COMP)") (class "Default")
      (node (ref "R14") (pin "2") (pinfunction "2_2") (pintype "passive"))
      (node (ref "R15") (pin "1") (pinfunction "1_1") (pintype "passive"))
      (node (ref "U3") (pin "5") (pinfunction "COMP_5") (pintype "bidirectional"))
    )
    (net (code "71") (name "Net-(U3-DVR)") (class "Default")
      (node (ref "R13") (pin "2") (pinfunction "2_2") (pintype "passive"))
      (node (ref "U3") (pin "1") (pinfunction "SWC_1") (pintype "bidirectional"))
      (node (ref "U3") (pin "7") (pinfunction "SEN_7") (pintype "bidirectional"))
      (node (ref "U3") (pin "8") (pinfunction "DVR_8") (pintype "bidirectional"))
    )
    (net (code "72") (name "Net-(U3-SWE)") (class "Default")
      (node (ref "D3") (pin "C") (pinfunction "C_C") (pintype "passive"))
      (node (ref "L1") (pin "1") (pinfunction "1_1") (pintype "passive"))
      (node (ref "U3") (pin "2") (pinfunction "SWE_2") (pintype "bidirectional"))
    )
    (net (code "73") (name "Net-(U3-TC)") (class "Default")
      (node (ref "C17") (pin "1") (pinfunction "1_1") (pintype "passive"))
      (node (ref "U3") (pin "3") (pinfunction "TC_3") (pintype "bidirectional"))
    )
    (net (code "74") (name "VCC") (class "Default")
      (node (ref "C15") (pin "+") (pinfunction "+_+") (pintype "passive"))
      (node (ref "D1") (pin "C") (pinfunction "C_C") (pintype "passive"))
      (node (ref "D4") (pin "C") (pinfunction "C_C") (pintype "passive"))
      (node (ref "R13") (pin "1") (pinfunction "1_1") (pintype "passive"))
      (node (ref "U3") (pin "6") (pinfunction "VCC_6") (pintype "bidirectional"))
    )
    (net (code "75") (name "unconnected-(IC1-OUT-Pad4)") (class "Default")
      (node (ref "IC1") (pin "4") (pinfunction "OUT_4") (pintype "output"))
    )
    (net (code "76") (name "unconnected-(M1-Pad2)") (class "Default")
      (node (ref "M1") (pin "2") (pinfunction "2_2") (pintype "passive"))
    )
    (net (code "77") (name "unconnected-(M2-Pad2)") (class "Default")
      (node (ref "M2") (pin "2") (pinfunction "2_2") (pintype "passive"))
    )
    (net (code "78") (name "unconnected-(M3-Pad2)") (class "Default")
      (node (ref "M3") (pin "2") (pinfunction "2_2") (pintype "passive"))
    )
    (net (code "79") (name "unconnected-(M4-Pad2)") (class "Default")
      (node (ref "M4") (pin "2") (pinfunction "2_2") (pintype "passive"))
    )
    (net (code "80") (name "unconnected-(M5-Pad2)") (class "Default")
      (node (ref "M5") (pin "2") (pinfunction "2_2") (pintype "passive"))
    )
    (net (code "81") (name "unconnected-(M6-Pad2)") (class "Default")
      (node (ref "M6") (pin "2") (pinfunction "2_2") (pintype "passive"))
    )
    (net (code "82") (name "unconnected-(M7-Pad2)") (class "Default")
      (node (ref "M7") (pin "2") (pinfunction "2_2") (pintype "passive"))
    )
    (net (code "83") (name "unconnected-(M8-Pad2)") (class "Default")
      (node (ref "M8") (pin "2") (pinfunction "2_2") (pintype "passive"))
    )
    (net (code "84") (name "unconnected-(MINI1-ID-Pad4)") (class "Default")
      (node (ref "MINI1") (pin "4") (pinfunction "ID_4") (pintype "passive"))
    )
    (net (code "85") (name "unconnected-(U4-RS-Pad8)") (class "Default")
      (node (ref "U4") (pin "8") (pinfunction "RS_8") (pintype "bidirectional"))
    )
    (net (code "86") (name "unconnected-(U4-VREF-Pad5)") (class "Default")
      (node (ref "U4") (pin "5") (pinfunction "VREF_5") (pintype "bidirectional"))
    )
  )
)
